# Sheet3.net
KiCad netlist of a schematic drawn in Altium Designer
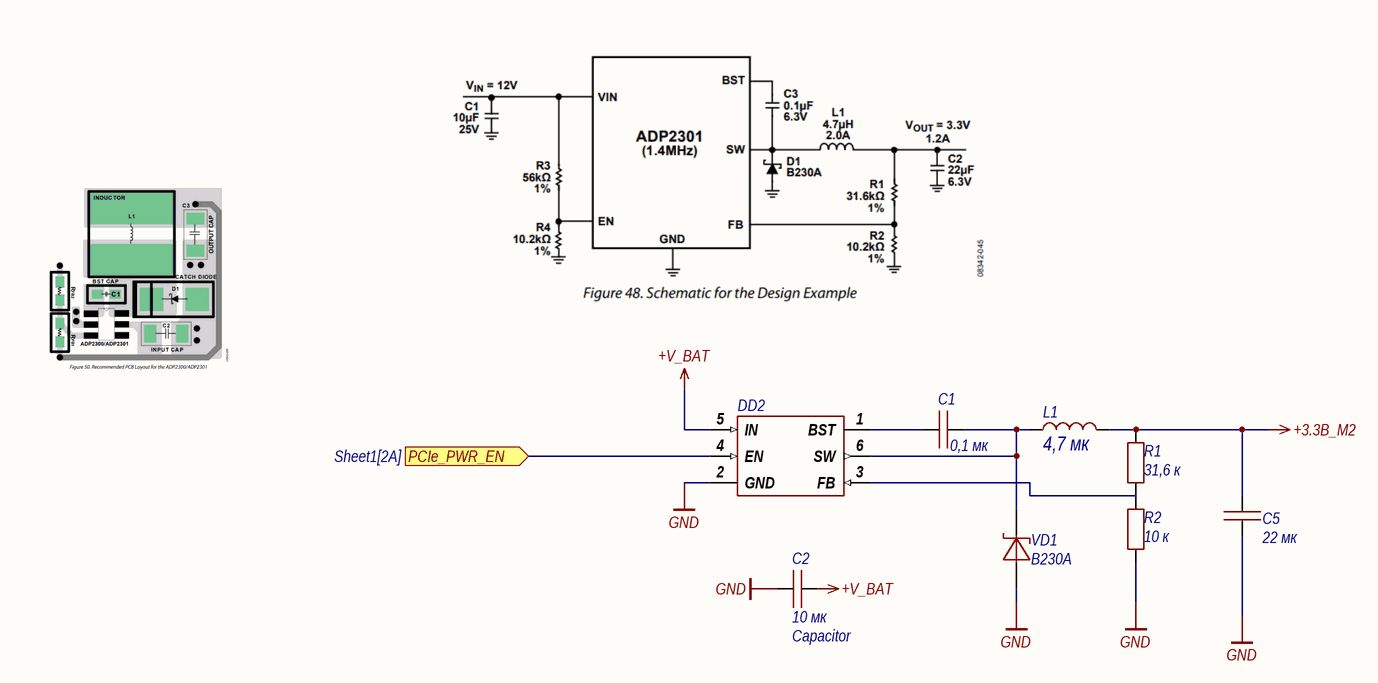
[diagram p0: Sheet3.SchDoc]

(export (version "E")
  (design (tool "Eeschema 10.0.6"))
  (components
    (comp (ref "C1")
      (value "0,1 мк")
      (footprint "0603C")
      (description "Конденсатор")
      (fields (field (name "PART NUMBER") "Capacitor_0,1u_10_50V_X7R_0603C") (field (name "TOLERANCE") "0,1"))
      (libsource (lib "Hydrolib") (part "Capacitor"))
    )
    (comp (ref "C2")
      (value "Capacitor")
      (footprint "1210C")
      (description "Конденсатор")
      (fields
        (field (name "ALTIUM_VALUE") "10 мк")
        (field (name "PART NUMBER") "Capacitor_10u_10_35V_X7R_1210C")
        (field (name "TOLERANCE") "0,1")
      )
      (libsource (lib "Hydrolib") (part "Capacitor"))
    )
    (comp (ref "C5")
      (value "22 мк")
      (footprint "1210C")
      (description "Конденсатор")
      (fields (field (name "PART NUMBER") "Capacitor_22u_10_25V_X7R_1210C") (field (name "TOLERANCE") "0,1"))
      (libsource (lib "Hydrolib") (part "Capacitor"))
    )
    (comp (ref "DD2")
      (value "Повышающий DC-DC преобразователь 2А 1.2МГц")
      (libsource (lib "Hydrolib") (part "ADP2300"))
    )
    (comp (ref "L1")
      (value "4,7 мк")
      (footprint "IHLP-2525")
      (description "ЧИП-индуктивность экранированная 4,7мкГн ±20% 5,5A 40мОм 2525")
      (fields (field (name "PART NUMBER") "IHLP2525CZER4R7M01"))
      (libsource (lib "Hydrolib") (part "Inductance"))
    )
    (comp (ref "R1")
      (value "31,6 к")
      (footprint "0603R")
      (description "Резистор номиналом 31,6 кОм и точностью 1%")
      (fields (field (name "PART NUMBER") "Resistor_31.6k_1_0603") (field (name "TOLERANCE") "1%"))
      (libsource (lib "") (part "Resistor_1"))
    )
    (comp (ref "R2")
      (value "10 к")
      (footprint "0603R")
      (description "Резистор номиналом 10 кОм и точностью 1%")
      (fields (field (name "PART NUMBER") "Resistor_10k_1_0603") (field (name "TOLERANCE") "1%"))
      (libsource (lib "Hydrolib") (part "Resistor"))
    )
    (comp (ref "VD1")
      (value "B230A")
      (footprint "SMA")
      (description "Диод шоттки на 40 В, ном. ток 2.1 А")
      (fields (field (name "PART NUMBER") "15MQ040N"))
      (libsource (lib "Hydrolib") (part "Schottky_diode"))
    )
  )
  (nets
    (net (code "1") (name "+3.3В_M2") (class "Default")
      (node (ref "C5") (pin "2") (pinfunction "2_2") (pintype "passive"))
      (node (ref "L1") (pin "2") (pinfunction "2_2") (pintype "passive"))
      (node (ref "R1") (pin "1") (pinfunction "1_1") (pintype "passive"))
    )
    (net (code "2") (name "+V_BAT") (class "Default")
      (node (ref "C2") (pin "2") (pinfunction "2_2") (pintype "passive"))
      (node (ref "DD2") (pin "5") (pinfunction "IN_5") (pintype "input"))
    )
    (net (code "3") (name "/PCIe_PWR_EN") (class "Default")
      (node (ref "DD2") (pin "4") (pinfunction "EN_4") (pintype "input"))
    )
    (net (code "4") (name "GND") (class "Default")
      (node (ref "C2") (pin "1") (pinfunction "1_1") (pintype "passive"))
      (node (ref "C5") (pin "1") (pinfunction "1_1") (pintype "passive"))
      (node (ref "DD2") (pin "2") (pinfunction "GND_2") (pintype "power_in"))
      (node (ref "R2") (pin "1") (pinfunction "1_1") (pintype "passive"))
      (node (ref "VD1") (pin "1") (pinfunction "1_1") (pintype "passive"))
    )
    (net (code "5") (name "Net-(DD2-BST)") (class "Default")
      (node (ref "C1") (pin "1") (pinfunction "1_1") (pintype "passive"))
      (node (ref "DD2") (pin "1") (pinfunction "BST_1") (pintype "power_in"))
    )
    (net (code "6") (name "Net-(DD2-FB)") (class "Default")
      (node (ref "DD2") (pin "3") (pinfunction "FB_3") (pintype "input"))
      (node (ref "R1") (pin "2") (pinfunction "2_2") (pintype "passive"))
      (node (ref "R2") (pin "2") (pinfunction "2_2") (pintype "passive"))
    )
    (net (code "7") (name "Net-(DD2-SW)") (class "Default")
      (node (ref "C1") (pin "2") (pinfunction "2_2") (pintype "passive"))
      (node (ref "DD2") (pin "6") (pinfunction "SW_6") (pintype "output"))
      (node (ref "L1") (pin "1") (pinfunction "1_1") (pintype "passive"))
      (node (ref "VD1") (pin "2") (pinfunction "2_2") (pintype "passive"))
    )
  )
)
